# Dev.net
KiCad netlist of a schematic drawn in Altium Designer
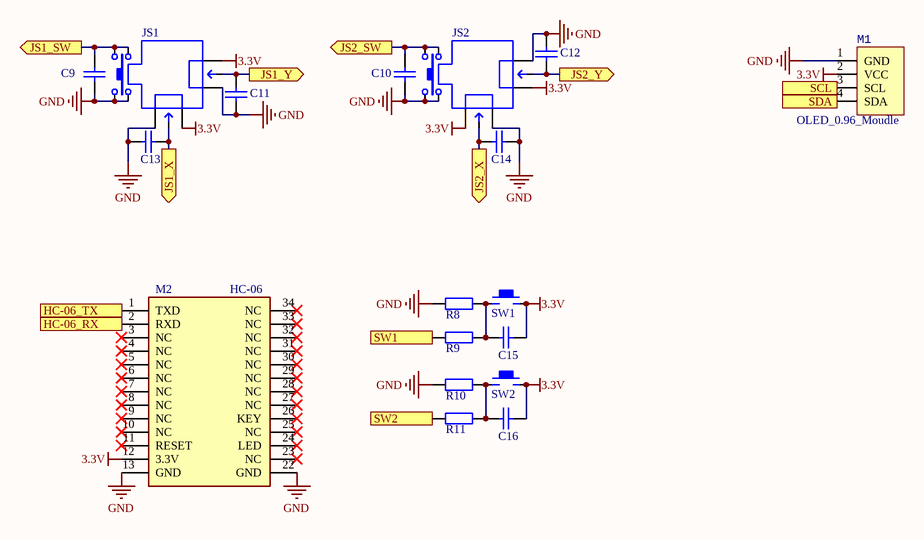
[diagram p0: Dev.SchDoc]

(export (version "E")
  (design (tool "Eeschema 10.0.6"))
  (components
    (comp (ref "C9")
      (value "220pF")
      (footprint "CAP-0603")
      (description "贴片电容")
      (libsource (lib "Power_Lib_Altium") (part "CAP"))
    )
    (comp (ref "C10")
      (value "220pF")
      (footprint "CAP-0603")
      (description "贴片电容")
      (libsource (lib "Power_Lib_Altium") (part "CAP"))
    )
    (comp (ref "C11")
      (value "220pF")
      (footprint "CAP-0603")
      (description "贴片电容")
      (libsource (lib "Power_Lib_Altium") (part "CAP"))
    )
    (comp (ref "C12")
      (value "220pF")
      (footprint "CAP-0603")
      (description "贴片电容")
      (libsource (lib "Power_Lib_Altium") (part "CAP"))
    )
    (comp (ref "C13")
      (value "220pF")
      (footprint "CAP-0603")
      (description "贴片电容")
      (libsource (lib "Power_Lib_Altium") (part "CAP"))
    )
    (comp (ref "C14")
      (value "220pF")
      (footprint "CAP-0603")
      (description "贴片电容")
      (libsource (lib "Power_Lib_Altium") (part "CAP"))
    )
    (comp (ref "C15")
      (value "100nF")
      (footprint "CAP-0603")
      (description "贴片电容")
      (libsource (lib "Power_Lib_Altium") (part "CAP"))
    )
    (comp (ref "C16")
      (value "100nF")
      (footprint "CAP-0603")
      (description "贴片电容")
      (libsource (lib "Power_Lib_Altium") (part "CAP"))
    )
    (comp (ref "JS1")
      (value "JoyStick")
      (footprint "JoyStick")
      (description "摇杆")
      (libsource (lib "Power_Lib_Altium") (part "JoyStick"))
    )
    (comp (ref "JS2")
      (value "JoyStick")
      (footprint "JoyStick")
      (description "摇杆")
      (libsource (lib "Power_Lib_Altium") (part "JoyStick"))
    )
    (comp (ref "M1")
      (value "OLED_0.96_Moudle")
      (footprint "OLED_0.96_Moudle")
      (description "OLED 屏")
      (libsource (lib "Power_Lib_Altium") (part "OLED_0.96_Moudle"))
    )
    (comp (ref "M2")
      (value "HC-06")
      (footprint "HC-05/06/08V15")
      (description "HC05/06 蓝牙模块（贴片）")
      (fields (field (name "MANUFACTURER_PART_NUMBER") "FT232RL") (field (name "RS PART NUMBER") "0406580P"))
      (libsource (lib "Power_Lib_Altium") (part "HC-05/06"))
    )
    (comp (ref "R8")
      (value "4.7k")
      (footprint "R-0603")
      (description "贴片电阻")
      (libsource (lib "Power_Lib_Altium") (part "RES"))
    )
    (comp (ref "R9")
      (value "1k")
      (footprint "R-0603")
      (description "贴片电阻")
      (libsource (lib "Power_Lib_Altium") (part "RES"))
    )
    (comp (ref "R10")
      (value "4.7k")
      (footprint "R-0603")
      (description "贴片电阻")
      (libsource (lib "Power_Lib_Altium") (part "RES"))
    )
    (comp (ref "R11")
      (value "1k")
      (footprint "R-0603")
      (description "贴片电阻")
      (libsource (lib "Power_Lib_Altium") (part "RES"))
    )
    (comp (ref "SW1")
      (value "KEY")
      (footprint "KEY_12*12*7.3")
      (description "按键开关")
      (libsource (lib "Power_Lib_Altium") (part "KEY"))
    )
    (comp (ref "SW2")
      (value "KEY")
      (footprint "KEY_12*12*7.3")
      (description "按键开关")
      (libsource (lib "Power_Lib_Altium") (part "KEY"))
    )
  )
  (nets
    (net (code "1") (name "/HC-06_RX") (class "Default")
      (node (ref "M2") (pin "2") (pinfunction "RXD_2") (pintype "passive"))
    )
    (net (code "2") (name "/HC-06_TX") (class "Default")
      (node (ref "M2") (pin "1") (pinfunction "TXD_1") (pintype "passive"))
    )
    (net (code "3") (name "/JS1_SW") (class "Default")
      (node (ref "C9") (pin "2") (pinfunction "2_2") (pintype "passive"))
      (node (ref "JS1") (pin "7") (pinfunction "7_7") (pintype "passive"))
      (node (ref "JS1") (pin "9") (pinfunction "9_9") (pintype "passive"))
    )
    (net (code "4") (name "/JS1_X") (class "Default")
      (node (ref "C13") (pin "1") (pinfunction "1_1") (pintype "passive"))
      (node (ref "JS1") (pin "2") (pinfunction "2_2") (pintype "passive"))
    )
    (net (code "5") (name "/JS1_Y") (class "Default")
      (node (ref "C11") (pin "2") (pinfunction "2_2") (pintype "passive"))
      (node (ref "JS1") (pin "5") (pinfunction "5_5") (pintype "passive"))
    )
    (net (code "6") (name "/JS2_SW") (class "Default")
      (node (ref "C10") (pin "2") (pinfunction "2_2") (pintype "passive"))
      (node (ref "JS2") (pin "7") (pinfunction "7_7") (pintype "passive"))
      (node (ref "JS2") (pin "9") (pinfunction "9_9") (pintype "passive"))
    )
    (net (code "7") (name "/JS2_X") (class "Default")
      (node (ref "C14") (pin "2") (pinfunction "2_2") (pintype "passive"))
      (node (ref "JS2") (pin "2") (pinfunction "2_2") (pintype "passive"))
    )
    (net (code "8") (name "/JS2_Y") (class "Default")
      (node (ref "C12") (pin "1") (pinfunction "1_1") (pintype "passive"))
      (node (ref "JS2") (pin "5") (pinfunction "5_5") (pintype "passive"))
    )
    (net (code "9") (name "/SCL") (class "Default")
      (node (ref "M1") (pin "3") (pinfunction "SCL_3") (pintype "passive"))
    )
    (net (code "10") (name "/SDA") (class "Default")
      (node (ref "M1") (pin "4") (pinfunction "SDA_4") (pintype "passive"))
    )
    (net (code "11") (name "/SW1") (class "Default")
      (node (ref "R9") (pin "1") (pinfunction "1_1") (pintype "passive"))
    )
    (net (code "12") (name "/SW2") (class "Default")
      (node (ref "R11") (pin "1") (pinfunction "1_1") (pintype "passive"))
    )
    (net (code "13") (name "3.3V") (class "Default")
      (node (ref "C15") (pin "2") (pinfunction "2_2") (pintype "passive"))
      (node (ref "C16") (pin "2") (pinfunction "2_2") (pintype "passive"))
      (node (ref "JS1") (pin "3") (pinfunction "3_3") (pintype "passive"))
      (node (ref "JS1") (pin "6") (pinfunction "6_6") (pintype "passive"))
      (node (ref "JS2") (pin "1") (pinfunction "1_1") (pintype "passive"))
      (node (ref "JS2") (pin "4") (pinfunction "4_4") (pintype "passive"))
      (node (ref "M1") (pin "2") (pinfunction "VCC_2") (pintype "passive"))
      (node (ref "M2") (pin "12") (pinfunction "3.3V_12") (pintype "passive"))
      (node (ref "SW1") (pin "2") (pinfunction "2_2") (pintype "passive"))
      (node (ref "SW2") (pin "2") (pinfunction "2_2") (pintype "passive"))
    )
    (net (code "14") (name "GND") (class "Default")
      (node (ref "C10") (pin "1") (pinfunction "1_1") (pintype "passive"))
      (node (ref "C11") (pin "1") (pinfunction "1_1") (pintype "passive"))
      (node (ref "C12") (pin "2") (pinfunction "2_2") (pintype "passive"))
      (node (ref "C13") (pin "2") (pinfunction "2_2") (pintype "passive"))
      (node (ref "C14") (pin "1") (pinfunction "1_1") (pintype "passive"))
      (node (ref "C9") (pin "1") (pinfunction "1_1") (pintype "passive"))
      (node (ref "JS1") (pin "1") (pinfunction "1_1") (pintype "passive"))
      (node (ref "JS1") (pin "10") (pinfunction "10_10") (pintype "passive"))
      (node (ref "JS1") (pin "4") (pinfunction "4_4") (pintype "passive"))
      (node (ref "JS1") (pin "8") (pinfunction "8_8") (pintype "passive"))
      (node (ref "JS2") (pin "10") (pinfunction "10_10") (pintype "passive"))
      (node (ref "JS2") (pin "3") (pinfunction "3_3") (pintype "passive"))
      (node (ref "JS2") (pin "6") (pinfunction "6_6") (pintype "passive"))
      (node (ref "JS2") (pin "8") (pinfunction "8_8") (pintype "passive"))
      (node (ref "M1") (pin "1") (pinfunction "GND_1") (pintype "passive"))
      (node (ref "M2") (pin "13") (pinfunction "GND_13") (pintype "passive"))
      (node (ref "M2") (pin "22") (pinfunction "GND_22") (pintype "passive"))
      (node (ref "R10") (pin "1") (pinfunction "1_1") (pintype "passive"))
      (node (ref "R8") (pin "1") (pinfunction "1_1") (pintype "passive"))
    )
    (net (code "15") (name "Net-(C15-Pad1)") (class "Default")
      (node (ref "C15") (pin "1") (pinfunction "1_1") (pintype "passive"))
      (node (ref "R8") (pin "2") (pinfunction "2_2") (pintype "passive"))
      (node (ref "R9") (pin "2") (pinfunction "2_2") (pintype "passive"))
      (node (ref "SW1") (pin "1") (pinfunction "1_1") (pintype "passive"))
    )
    (net (code "16") (name "Net-(C16-Pad1)") (class "Default")
      (node (ref "C16") (pin "1") (pinfunction "1_1") (pintype "passive"))
      (node (ref "R10") (pin "2") (pinfunction "2_2") (pintype "passive"))
      (node (ref "R11") (pin "2") (pinfunction "2_2") (pintype "passive"))
      (node (ref "SW2") (pin "1") (pinfunction "1_1") (pintype "passive"))
    )
    (net (code "17") (name "unconnected-(M2-KEY-Pad26)") (class "Default")
      (node (ref "M2") (pin "26") (pinfunction "KEY_26") (pintype "passive+no_connect"))
    )
    (net (code "18") (name "unconnected-(M2-LED-Pad24)") (class "Default")
      (node (ref "M2") (pin "24") (pinfunction "LED_24") (pintype "passive+no_connect"))
    )
    (net (code "19") (name "unconnected-(M2-NC-Pad3)") (class "Default")
      (node (ref "M2") (pin "3") (pinfunction "NC_3") (pintype "passive+no_connect"))
    )
    (net (code "20") (name "unconnected-(M2-NC-Pad4)") (class "Default")
      (node (ref "M2") (pin "4") (pinfunction "NC_4") (pintype "power_in+no_connect"))
    )
    (net (code "21") (name "unconnected-(M2-NC-Pad5)") (class "Default")
      (node (ref "M2") (pin "5") (pinfunction "NC_5") (pintype "passive+no_connect"))
    )
    (net (code "22") (name "unconnected-(M2-NC-Pad6)") (class "Default")
      (node (ref "M2") (pin "6") (pinfunction "NC_6") (pintype "passive+no_connect"))
    )
    (net (code "23") (name "unconnected-(M2-NC-Pad7)") (class "Default")
      (node (ref "M2") (pin "7") (pinfunction "NC_7") (pintype "power_in+no_connect"))
    )
    (net (code "24") (name "unconnected-(M2-NC-Pad8)") (class "Default")
      (node (ref "M2") (pin "8") (pinfunction "NC_8") (pintype "passive+no_connect"))
    )
    (net (code "25") (name "unconnected-(M2-NC-Pad9)") (class "Default")
      (node (ref "M2") (pin "9") (pinfunction "NC_9") (pintype "passive+no_connect"))
    )
    (net (code "26") (name "unconnected-(M2-NC-Pad10)") (class "Default")
      (node (ref "M2") (pin "10") (pinfunction "NC_10") (pintype "passive+no_connect"))
    )
    (net (code "27") (name "unconnected-(M2-NC-Pad23)") (class "Default")
      (node (ref "M2") (pin "23") (pinfunction "NC_23") (pintype "passive+no_connect"))
    )
    (net (code "28") (name "unconnected-(M2-NC-Pad25)") (class "Default")
      (node (ref "M2") (pin "25") (pinfunction "NC_25") (pintype "passive+no_connect"))
    )
    (net (code "29") (name "unconnected-(M2-NC-Pad27)") (class "Default")
      (node (ref "M2") (pin "27") (pinfunction "NC_27") (pintype "passive+no_connect"))
    )
    (net (code "30") (name "unconnected-(M2-NC-Pad28)") (class "Default")
      (node (ref "M2") (pin "28") (pinfunction "NC_28") (pintype "passive+no_connect"))
    )
    (net (code "31") (name "unconnected-(M2-NC-Pad29)") (class "Default")
      (node (ref "M2") (pin "29") (pinfunction "NC_29") (pintype "passive+no_connect"))
    )
    (net (code "32") (name "unconnected-(M2-NC-Pad30)") (class "Default")
      (node (ref "M2") (pin "30") (pinfunction "NC_30") (pintype "passive+no_connect"))
    )
    (net (code "33") (name "unconnected-(M2-NC-Pad31)") (class "Default")
      (node (ref "M2") (pin "31") (pinfunction "NC_31") (pintype "passive+no_connect"))
    )
    (net (code "34") (name "unconnected-(M2-NC-Pad32)") (class "Default")
      (node (ref "M2") (pin "32") (pinfunction "NC_32") (pintype "passive+no_connect"))
    )
    (net (code "35") (name "unconnected-(M2-NC-Pad33)") (class "Default")
      (node (ref "M2") (pin "33") (pinfunction "NC_33") (pintype "passive+no_connect"))
    )
    (net (code "36") (name "unconnected-(M2-NC-Pad34)") (class "Default")
      (node (ref "M2") (pin "34") (pinfunction "NC_34") (pintype "passive+no_connect"))
    )
    (net (code "37") (name "unconnected-(M2-RESET-Pad11)") (class "Default")
      (node (ref "M2") (pin "11") (pinfunction "RESET_11") (pintype "passive+no_connect"))
    )
  )
)
